# workshop.net
KiCad netlist of a schematic drawn in EAGLE
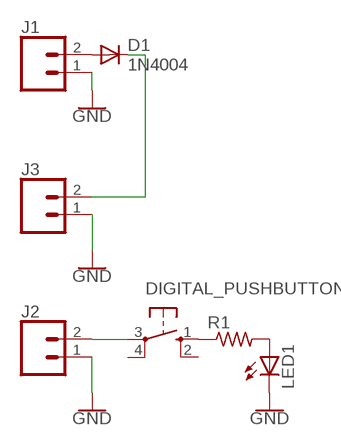
[diagram p0: schematic, sheet 1]

(export (version "E")
  (design (tool "Eeschema 10.0.6"))
  (components
    (comp (ref "D1")
      (value "1N4004")
      (footprint "eagle-import:DO41-10")
      (libsource (lib "eagle-import") (part "1N4004"))
    )
    (comp (ref "DIGITAL_PUSHBUTTON")
      (value "10-XX")
      (footprint "eagle-import:B3F-10XX")
      (fields (field (name "MPN") "B3F-1000"))
      (libsource (lib "eagle-import") (part "10-XX"))
    )
    (comp (ref "J1")
      (value "CONN_02")
      (footprint "eagle-import:1X02")
      (libsource (lib "eagle-import") (part "CONN_02"))
    )
    (comp (ref "J2")
      (value "CONN_02")
      (footprint "eagle-import:1X02")
      (libsource (lib "eagle-import") (part "CONN_02"))
    )
    (comp (ref "J3")
      (value "CONN_02")
      (footprint "eagle-import:1X02")
      (libsource (lib "eagle-import") (part "CONN_02"))
    )
    (comp (ref "LED1")
      (value "LED5MM")
      (footprint "eagle-import:LED5MM")
      (libsource (lib "eagle-import") (part "LED5MM"))
    )
    (comp (ref "R1")
      (value "R-US_0309/12")
      (footprint "eagle-import:0309_12")
      (libsource (lib "eagle-import") (part "R-US_0309/12"))
    )
  )
  (nets
    (net (code "1") (name "GND") (class "Default")
      (node (ref "J1") (pin "1") (pinfunction "1_1") (pintype "passive"))
      (node (ref "J2") (pin "1") (pinfunction "1_1") (pintype "passive"))
      (node (ref "J3") (pin "1") (pinfunction "1_1") (pintype "passive"))
      (node (ref "LED1") (pin "K") (pinfunction "C_K") (pintype "passive"))
    )
    (net (code "2") (name "Net-(D1-PadA)") (class "Default")
      (node (ref "D1") (pin "A") (pinfunction "A_A") (pintype "passive"))
      (node (ref "J1") (pin "2") (pinfunction "2_2") (pintype "passive"))
    )
    (net (code "3") (name "Net-(D1-PadC)") (class "Default")
      (node (ref "D1") (pin "C") (pinfunction "C_C") (pintype "passive"))
      (node (ref "J3") (pin "2") (pinfunction "2_2") (pintype "passive"))
    )
    (net (code "4") (name "Net-(DIGITAL_PUSHBUTTON-P)") (class "Default")
      (node (ref "DIGITAL_PUSHBUTTON") (pin "3") (pinfunction "P_3") (pintype "passive"))
      (node (ref "J2") (pin "2") (pinfunction "2_2") (pintype "passive"))
    )
    (net (code "5") (name "Net-(DIGITAL_PUSHBUTTON-S)") (class "Default")
      (node (ref "DIGITAL_PUSHBUTTON") (pin "1") (pinfunction "S_1") (pintype "passive"))
      (node (ref "R1") (pin "1") (pinfunction "1_1") (pintype "passive"))
    )
    (net (code "6") (name "Net-(LED1-PadA)") (class "Default")
      (node (ref "LED1") (pin "A") (pinfunction "A_A") (pintype "passive"))
      (node (ref "R1") (pin "2") (pinfunction "2_2") (pintype "passive"))
    )
    (net (code "7") (name "unconnected-(DIGITAL_PUSHBUTTON-P1-Pad4)") (class "Default")
      (node (ref "DIGITAL_PUSHBUTTON") (pin "4") (pinfunction "P1_4") (pintype "passive"))
    )
    (net (code "8") (name "unconnected-(DIGITAL_PUSHBUTTON-S1-Pad2)") (class "Default")
      (node (ref "DIGITAL_PUSHBUTTON") (pin "2") (pinfunction "S1_2") (pintype "passive"))
    )
  )
)
